# schematic.net
KiCad netlist of a schematic drawn in EAGLE
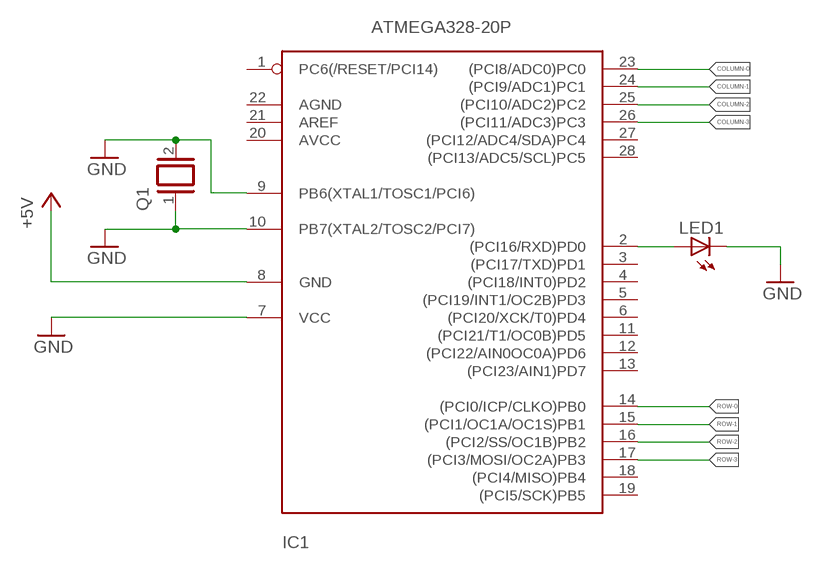
[diagram p0: schematic, sheet 1]

(export (version "E")
  (design (tool "Eeschema 10.0.6"))
  (components
    (comp (ref "IC1")
      (value "ATMEGA328-20P")
      (footprint "eagle-import:DIL28-3")
      (libsource (lib "eagle-import") (part "ATMEGA328P-20"))
    )
    (comp (ref "LED1")
      (value "LEDB155")
      (footprint "eagle-import:Q62902-B155")
      (libsource (lib "eagle-import") (part "LEDB155"))
    )
    (comp (ref "Q1")
      (value "XTAL")
      (footprint "eagle-import:Q")
      (libsource (lib "eagle-import") (part "XTAL"))
    )
  )
  (nets
    (net (code "1") (name "+5V") (class "Default")
      (node (ref "IC1") (pin "8") (pinfunction "GND_8") (pintype "bidirectional"))
    )
    (net (code "2") (name "COLUMN-0") (class "Default")
      (node (ref "IC1") (pin "23") (pinfunction "(PCI8/ADC0)PC0_23") (pintype "bidirectional"))
    )
    (net (code "3") (name "COLUMN-1") (class "Default")
      (node (ref "IC1") (pin "24") (pinfunction "(PCI9/ADC1)PC1_24") (pintype "bidirectional"))
    )
    (net (code "4") (name "COLUMN-2") (class "Default")
      (node (ref "IC1") (pin "25") (pinfunction "(PCI10/ADC2)PC2_25") (pintype "bidirectional"))
    )
    (net (code "5") (name "COLUMN-3") (class "Default")
      (node (ref "IC1") (pin "26") (pinfunction "(PCI11/ADC3)PC3_26") (pintype "bidirectional"))
    )
    (net (code "6") (name "GND") (class "Default")
      (node (ref "IC1") (pin "10") (pinfunction "PB7(XTAL2/TOSC2/PCI7)_10") (pintype "bidirectional"))
      (node (ref "IC1") (pin "7") (pinfunction "VCC_7") (pintype "bidirectional"))
      (node (ref "IC1") (pin "9") (pinfunction "PB6(XTAL1/TOSC1/PCI6)_9") (pintype "bidirectional"))
      (node (ref "LED1") (pin "K") (pinfunction "C_K") (pintype "passive"))
      (node (ref "Q1") (pin "1") (pinfunction "1_1") (pintype "passive"))
      (node (ref "Q1") (pin "2") (pinfunction "2_2") (pintype "passive"))
    )
    (net (code "7") (name "Net-(IC1-(PCI16{slash}RXD)PD0)") (class "Default")
      (node (ref "IC1") (pin "2") (pinfunction "(PCI16/RXD)PD0_2") (pintype "bidirectional"))
      (node (ref "LED1") (pin "A") (pinfunction "A_A") (pintype "passive"))
    )
    (net (code "8") (name "ROW-0") (class "Default")
      (node (ref "IC1") (pin "14") (pinfunction "(PCI0/ICP/CLKO)PB0_14") (pintype "bidirectional"))
    )
    (net (code "9") (name "ROW-1") (class "Default")
      (node (ref "IC1") (pin "15") (pinfunction "(PCI1/OC1A/OC1S)PB1_15") (pintype "bidirectional"))
    )
    (net (code "10") (name "ROW-2") (class "Default")
      (node (ref "IC1") (pin "16") (pinfunction "(PCI2/SS/OC1B)PB2_16") (pintype "bidirectional"))
    )
    (net (code "11") (name "ROW-3") (class "Default")
      (node (ref "IC1") (pin "17") (pinfunction "(PCI3/MOSI/OC2A)PB3_17") (pintype "bidirectional"))
    )
    (net (code "12") (name "unconnected-(IC1-(PCI4{slash}MISO)PB4-Pad18)") (class "Default")
      (node (ref "IC1") (pin "18") (pinfunction "(PCI4/MISO)PB4_18") (pintype "bidirectional"))
    )
    (net (code "13") (name "unconnected-(IC1-(PCI5{slash}SCK)PB5-Pad19)") (class "Default")
      (node (ref "IC1") (pin "19") (pinfunction "(PCI5/SCK)PB5_19") (pintype "bidirectional"))
    )
    (net (code "14") (name "unconnected-(IC1-(PCI12{slash}ADC4{slash}SDA)PC4-Pad27)") (class "Default")
      (node (ref "IC1") (pin "27") (pinfunction "(PCI12/ADC4/SDA)PC4_27") (pintype "bidirectional"))
    )
    (net (code "15") (name "unconnected-(IC1-(PCI13{slash}ADC5{slash}SCL)PC5-Pad28)") (class "Default")
      (node (ref "IC1") (pin "28") (pinfunction "(PCI13/ADC5/SCL)PC5_28") (pintype "bidirectional"))
    )
    (net (code "16") (name "unconnected-(IC1-(PCI17{slash}TXD)PD1-Pad3)") (class "Default")
      (node (ref "IC1") (pin "3") (pinfunction "(PCI17/TXD)PD1_3") (pintype "bidirectional"))
    )
    (net (code "17") (name "unconnected-(IC1-(PCI18{slash}INT0)PD2-Pad4)") (class "Default")
      (node (ref "IC1") (pin "4") (pinfunction "(PCI18/INT0)PD2_4") (pintype "bidirectional"))
    )
    (net (code "18") (name "unconnected-(IC1-(PCI19{slash}INT1{slash}OC2B)PD3-Pad5)") (class "Default")
      (node (ref "IC1") (pin "5") (pinfunction "(PCI19/INT1/OC2B)PD3_5") (pintype "bidirectional"))
    )
    (net (code "19") (name "unconnected-(IC1-(PCI20{slash}XCK{slash}T0)PD4-Pad6)") (class "Default")
      (node (ref "IC1") (pin "6") (pinfunction "(PCI20/XCK/T0)PD4_6") (pintype "bidirectional"))
    )
    (net (code "20") (name "unconnected-(IC1-(PCI21{slash}T1{slash}OC0B)PD5-Pad11)") (class "Default")
      (node (ref "IC1") (pin "11") (pinfunction "(PCI21/T1/OC0B)PD5_11") (pintype "bidirectional"))
    )
    (net (code "21") (name "unconnected-(IC1-(PCI22{slash}AIN0OC0A)PD6-Pad12)") (class "Default")
      (node (ref "IC1") (pin "12") (pinfunction "(PCI22/AIN0OC0A)PD6_12") (pintype "bidirectional"))
    )
    (net (code "22") (name "unconnected-(IC1-(PCI23{slash}AIN1)PD7-Pad13)") (class "Default")
      (node (ref "IC1") (pin "13") (pinfunction "(PCI23/AIN1)PD7_13") (pintype "bidirectional"))
    )
    (net (code "23") (name "unconnected-(IC1-AGND-Pad22)") (class "Default")
      (node (ref "IC1") (pin "22") (pinfunction "AGND_22") (pintype "bidirectional"))
    )
    (net (code "24") (name "unconnected-(IC1-AREF-Pad21)") (class "Default")
      (node (ref "IC1") (pin "21") (pinfunction "AREF_21") (pintype "bidirectional"))
    )
    (net (code "25") (name "unconnected-(IC1-AVCC-Pad20)") (class "Default")
      (node (ref "IC1") (pin "20") (pinfunction "AVCC_20") (pintype "bidirectional"))
    )
    (net (code "26") (name "unconnected-(IC1-PC6({slash}RESET{slash}PCI14)-Pad1)") (class "Default")
      (node (ref "IC1") (pin "1") (pinfunction "PC6(/RESET/PCI14)_1") (pintype "bidirectional"))
    )
  )
)
